# 5-NAND_FLASH.net
KiCad netlist of a schematic drawn in Altium Designer
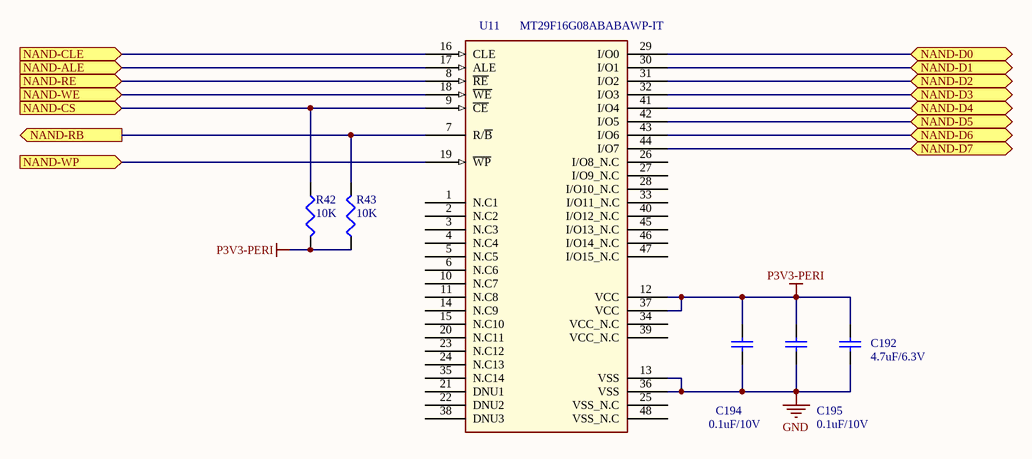
[diagram p0: 5-NAND_FLASH.SchDoc]

(export (version "E")
  (design (tool "Eeschema 10.0.6"))
  (components
    (comp (ref "C192")
      (value "4.7uF/6.3V")
      (footprint "0603_CC")
      (description "Capacitor")
      (fields (field (name "PUBLISHER") "Altium Limited"))
      (libsource (lib "Miscellaneous Devices") (part "Cap"))
    )
    (comp (ref "C194")
      (value "0.1uF/10V")
      (footprint "0402_CC")
      (description "Capacitor")
      (fields (field (name "PUBLISHER") "Altium Limited"))
      (libsource (lib "Miscellaneous Devices") (part "Cap"))
    )
    (comp (ref "C195")
      (value "0.1uF/10V")
      (footprint "0402_CC")
      (description "Capacitor")
      (fields (field (name "PUBLISHER") "Altium Limited"))
      (libsource (lib "Miscellaneous Devices") (part "Cap"))
    )
    (comp (ref "R42")
      (value "10K")
      (footprint "0402_CC")
      (description "Resistor")
      (fields (field (name "PUBLISHER") "Altium Limited"))
      (libsource (lib "Miscellaneous Devices") (part "Res3"))
    )
    (comp (ref "R43")
      (value "10K")
      (footprint "0402_CC")
      (description "Resistor")
      (fields (field (name "PUBLISHER") "Altium Limited"))
      (libsource (lib "Miscellaneous Devices") (part "Res3"))
    )
    (comp (ref "U11") (value "MT29F16G08ABABAWP-IT") (libsource (lib "*") (part "MT29F2GxxAAD")))
  )
  (nets
    (net (code "1") (name "/NAND-ALE") (class "Default")
      (node (ref "U11") (pin "17") (pinfunction "ALE_17") (pintype "input"))
    )
    (net (code "2") (name "/NAND-CLE") (class "Default")
      (node (ref "U11") (pin "16") (pinfunction "CLE_16") (pintype "input"))
    )
    (net (code "3") (name "/NAND-CS") (class "Default")
      (node (ref "R42") (pin "1") (pinfunction "1_1") (pintype "passive"))
      (node (ref "U11") (pin "9") (pinfunction "~{CE}_9") (pintype "input"))
    )
    (net (code "4") (name "/NAND-D0") (class "Default")
      (node (ref "U11") (pin "29") (pinfunction "I/O0_29") (pintype "tri_state"))
    )
    (net (code "5") (name "/NAND-D1") (class "Default")
      (node (ref "U11") (pin "30") (pinfunction "I/O1_30") (pintype "tri_state"))
    )
    (net (code "6") (name "/NAND-D2") (class "Default")
      (node (ref "U11") (pin "31") (pinfunction "I/O2_31") (pintype "tri_state"))
    )
    (net (code "7") (name "/NAND-D3") (class "Default")
      (node (ref "U11") (pin "32") (pinfunction "I/O3_32") (pintype "tri_state"))
    )
    (net (code "8") (name "/NAND-D4") (class "Default")
      (node (ref "U11") (pin "41") (pinfunction "I/O4_41") (pintype "tri_state"))
    )
    (net (code "9") (name "/NAND-D5") (class "Default")
      (node (ref "U11") (pin "42") (pinfunction "I/O5_42") (pintype "tri_state"))
    )
    (net (code "10") (name "/NAND-D6") (class "Default")
      (node (ref "U11") (pin "43") (pinfunction "I/O6_43") (pintype "tri_state"))
    )
    (net (code "11") (name "/NAND-D7") (class "Default")
      (node (ref "U11") (pin "44") (pinfunction "I/O7_44") (pintype "tri_state"))
    )
    (net (code "12") (name "/NAND-RB") (class "Default")
      (node (ref "R43") (pin "2") (pinfunction "2_2") (pintype "passive"))
      (node (ref "U11") (pin "7") (pinfunction "R/~{B}_7") (pintype "open_collector"))
    )
    (net (code "13") (name "/NAND-RE") (class "Default")
      (node (ref "U11") (pin "8") (pinfunction "~{RE}_8") (pintype "input"))
    )
    (net (code "14") (name "/NAND-WE") (class "Default")
      (node (ref "U11") (pin "18") (pinfunction "~{WE}_18") (pintype "input"))
    )
    (net (code "15") (name "/NAND-WP") (class "Default")
      (node (ref "U11") (pin "19") (pinfunction "~{WP}_19") (pintype "input"))
    )
    (net (code "16") (name "GND") (class "Default")
      (node (ref "C192") (pin "2") (pinfunction "2_2") (pintype "passive"))
      (node (ref "C194") (pin "2") (pinfunction "2_2") (pintype "passive"))
      (node (ref "C195") (pin "2") (pinfunction "2_2") (pintype "passive"))
      (node (ref "U11") (pin "13") (pinfunction "VSS_13") (pintype "power_in"))
      (node (ref "U11") (pin "36") (pinfunction "VSS_36") (pintype "power_in"))
    )
    (net (code "17") (name "P3V3-PERI") (class "Default")
      (node (ref "C192") (pin "1") (pinfunction "1_1") (pintype "passive"))
      (node (ref "C194") (pin "1") (pinfunction "1_1") (pintype "passive"))
      (node (ref "C195") (pin "1") (pinfunction "1_1") (pintype "passive"))
      (node (ref "R42") (pin "2") (pinfunction "2_2") (pintype "passive"))
      (node (ref "R43") (pin "1") (pinfunction "1_1") (pintype "passive"))
      (node (ref "U11") (pin "12") (pinfunction "VCC_12") (pintype "power_in"))
      (node (ref "U11") (pin "37") (pinfunction "VCC_37") (pintype "power_in"))
    )
    (net (code "18") (name "unconnected-(U11-DNU1-Pad21)") (class "Default")
      (node (ref "U11") (pin "21") (pinfunction "DNU1_21") (pintype "passive"))
    )
    (net (code "19") (name "unconnected-(U11-DNU2-Pad22)") (class "Default")
      (node (ref "U11") (pin "22") (pinfunction "DNU2_22") (pintype "passive"))
    )
    (net (code "20") (name "unconnected-(U11-DNU3-Pad38)") (class "Default")
      (node (ref "U11") (pin "38") (pinfunction "DNU3_38") (pintype "passive"))
    )
    (net (code "21") (name "unconnected-(U11-I{slash}O8_N.C-Pad26)") (class "Default")
      (node (ref "U11") (pin "26") (pinfunction "I/O8_N.C_26") (pintype "passive"))
    )
    (net (code "22") (name "unconnected-(U11-I{slash}O9_N.C-Pad27)") (class "Default")
      (node (ref "U11") (pin "27") (pinfunction "I/O9_N.C_27") (pintype "passive"))
    )
    (net (code "23") (name "unconnected-(U11-I{slash}O10_N.C-Pad28)") (class "Default")
      (node (ref "U11") (pin "28") (pinfunction "I/O10_N.C_28") (pintype "passive"))
    )
    (net (code "24") (name "unconnected-(U11-I{slash}O11_N.C-Pad33)") (class "Default")
      (node (ref "U11") (pin "33") (pinfunction "I/O11_N.C_33") (pintype "passive"))
    )
    (net (code "25") (name "unconnected-(U11-I{slash}O12_N.C-Pad40)") (class "Default")
      (node (ref "U11") (pin "40") (pinfunction "I/O12_N.C_40") (pintype "passive"))
    )
    (net (code "26") (name "unconnected-(U11-I{slash}O13_N.C-Pad45)") (class "Default")
      (node (ref "U11") (pin "45") (pinfunction "I/O13_N.C_45") (pintype "passive"))
    )
    (net (code "27") (name "unconnected-(U11-I{slash}O14_N.C-Pad46)") (class "Default")
      (node (ref "U11") (pin "46") (pinfunction "I/O14_N.C_46") (pintype "passive"))
    )
    (net (code "28") (name "unconnected-(U11-I{slash}O15_N.C-Pad47)") (class "Default")
      (node (ref "U11") (pin "47") (pinfunction "I/O15_N.C_47") (pintype "passive"))
    )
    (net (code "29") (name "unconnected-(U11-N.C1-Pad1)") (class "Default")
      (node (ref "U11") (pin "1") (pinfunction "N.C1_1") (pintype "passive"))
    )
    (net (code "30") (name "unconnected-(U11-N.C2-Pad2)") (class "Default")
      (node (ref "U11") (pin "2") (pinfunction "N.C2_2") (pintype "passive"))
    )
    (net (code "31") (name "unconnected-(U11-N.C3-Pad3)") (class "Default")
      (node (ref "U11") (pin "3") (pinfunction "N.C3_3") (pintype "passive"))
    )
    (net (code "32") (name "unconnected-(U11-N.C4-Pad4)") (class "Default")
      (node (ref "U11") (pin "4") (pinfunction "N.C4_4") (pintype "passive"))
    )
    (net (code "33") (name "unconnected-(U11-N.C5-Pad5)") (class "Default")
      (node (ref "U11") (pin "5") (pinfunction "N.C5_5") (pintype "passive"))
    )
    (net (code "34") (name "unconnected-(U11-N.C6-Pad6)") (class "Default")
      (node (ref "U11") (pin "6") (pinfunction "N.C6_6") (pintype "passive"))
    )
    (net (code "35") (name "unconnected-(U11-N.C7-Pad10)") (class "Default")
      (node (ref "U11") (pin "10") (pinfunction "N.C7_10") (pintype "passive"))
    )
    (net (code "36") (name "unconnected-(U11-N.C8-Pad11)") (class "Default")
      (node (ref "U11") (pin "11") (pinfunction "N.C8_11") (pintype "passive"))
    )
    (net (code "37") (name "unconnected-(U11-N.C9-Pad14)") (class "Default")
      (node (ref "U11") (pin "14") (pinfunction "N.C9_14") (pintype "passive"))
    )
    (net (code "38") (name "unconnected-(U11-N.C10-Pad15)") (class "Default")
      (node (ref "U11") (pin "15") (pinfunction "N.C10_15") (pintype "passive"))
    )
    (net (code "39") (name "unconnected-(U11-N.C11-Pad20)") (class "Default")
      (node (ref "U11") (pin "20") (pinfunction "N.C11_20") (pintype "passive"))
    )
    (net (code "40") (name "unconnected-(U11-N.C12-Pad23)") (class "Default")
      (node (ref "U11") (pin "23") (pinfunction "N.C12_23") (pintype "passive"))
    )
    (net (code "41") (name "unconnected-(U11-N.C13-Pad24)") (class "Default")
      (node (ref "U11") (pin "24") (pinfunction "N.C13_24") (pintype "passive"))
    )
    (net (code "42") (name "unconnected-(U11-N.C14-Pad35)") (class "Default")
      (node (ref "U11") (pin "35") (pinfunction "N.C14_35") (pintype "passive"))
    )
    (net (code "43") (name "unconnected-(U11-VCC_N.C-Pad34)") (class "Default")
      (node (ref "U11") (pin "34") (pinfunction "VCC_N.C_34") (pintype "power_in"))
    )
    (net (code "44") (name "unconnected-(U11-VCC_N.C-Pad39)") (class "Default")
      (node (ref "U11") (pin "39") (pinfunction "VCC_N.C_39") (pintype "power_in"))
    )
    (net (code "45") (name "unconnected-(U11-VSS_N.C-Pad25)") (class "Default")
      (node (ref "U11") (pin "25") (pinfunction "VSS_N.C_25") (pintype "power_in"))
    )
    (net (code "46") (name "unconnected-(U11-VSS_N.C-Pad48)") (class "Default")
      (node (ref "U11") (pin "48") (pinfunction "VSS_N.C_48") (pintype "power_in"))
    )
  )
)
